# 03_SENSORS.net
KiCad netlist of a schematic drawn in Altium Designer
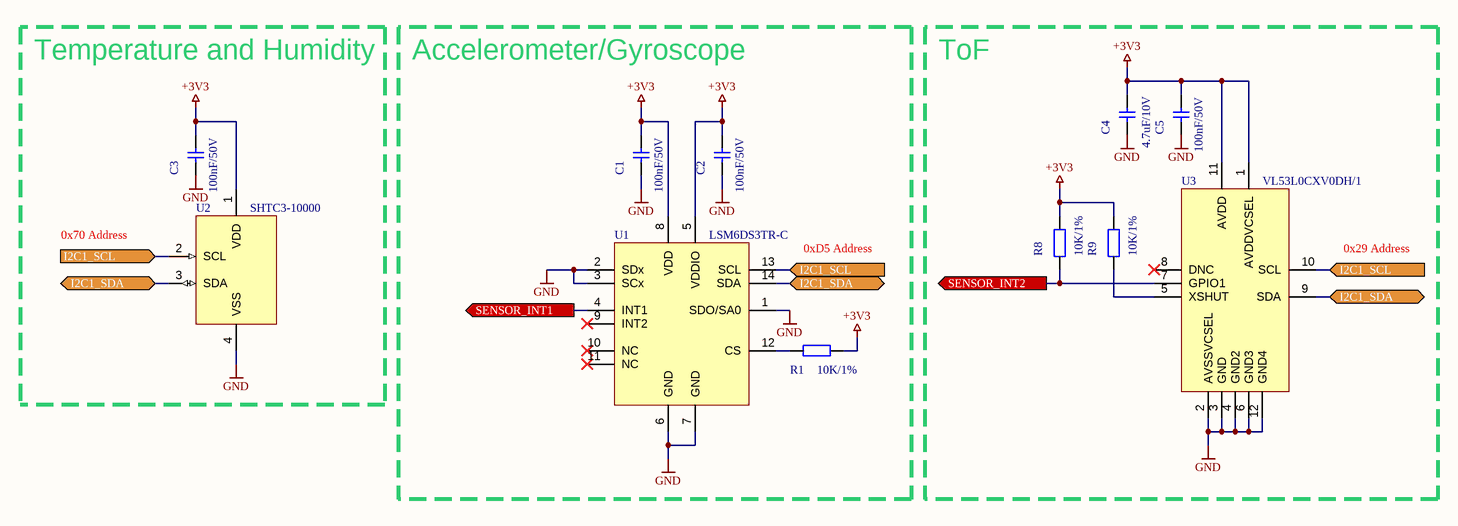
[diagram p0: 03 SENSORS.SchDoc]

(export (version "E")
  (design (tool "Eeschema 10.0.6"))
  (components
    (comp (ref "C1")
      (value "100nF/50V")
      (footprint "CAPC1005X06N")
      (description "16V 100nF X7R ±10% 0402  Multilayer Ceramic Capacitors MLCC - SMD/SMT ROHS")
      (fields
        (field (name "MANUFACTURER") "Samsung Electro-Mechanics")
        (field (name "MFR_PART_NUMBER") "CL05B104KO5NNNC")
      )
      (libsource (lib "altium_symbol") (part "CL05B104KO5NNNC"))
    )
    (comp (ref "C2")
      (value "100nF/50V")
      (footprint "CAPC1005X06N")
      (description "16V 100nF X7R ±10% 0402  Multilayer Ceramic Capacitors MLCC - SMD/SMT ROHS")
      (fields
        (field (name "MANUFACTURER") "Samsung Electro-Mechanics")
        (field (name "MFR_PART_NUMBER") "CL05B104KO5NNNC")
      )
      (libsource (lib "altium_symbol") (part "CL05B104KO5NNNC"))
    )
    (comp (ref "C3")
      (value "100nF/50V")
      (footprint "CAPC1005X06N")
      (description "16V 100nF X7R ±10% 0402  Multilayer Ceramic Capacitors MLCC - SMD/SMT ROHS")
      (fields
        (field (name "MANUFACTURER") "Samsung Electro-Mechanics")
        (field (name "MFR_PART_NUMBER") "CL05B104KO5NNNC")
      )
      (libsource (lib "altium_symbol") (part "CL05B104KO5NNNC"))
    )
    (comp (ref "C4")
      (value "4.7uF/10V")
      (footprint "CAPC1005X06N")
      (description "10V 4.7uF X5R ±20% 0402  Multilayer Ceramic Capacitors MLCC - SMD/SMT ROHS")
      (fields
        (field (name "MANUFACTURER") "Samsung Electro-Mechanics")
        (field (name "MFR_PART_NUMBER") "CL05A475MP5NRNC")
      )
      (libsource (lib "altium_symbol") (part "CL05A475MP5NRNC"))
    )
    (comp (ref "C5")
      (value "100nF/50V")
      (footprint "CAPC1005X06N")
      (description "16V 100nF X7R ±10% 0402  Multilayer Ceramic Capacitors MLCC - SMD/SMT ROHS")
      (fields
        (field (name "MANUFACTURER") "Samsung Electro-Mechanics")
        (field (name "MFR_PART_NUMBER") "CL05B104KO5NNNC")
      )
      (libsource (lib "altium_symbol") (part "CL05B104KO5NNNC"))
    )
    (comp (ref "R1")
      (value "10K/1%")
      (footprint "RESC1005X04N")
      (fields
        (field (name "MANUFACTURER") "UNI-ROYAL(Uniroyal Elec)")
        (field (name "MFR_PART_NUMBER") "0402WGF1002TCE")
      )
      (libsource (lib "altium_symbol") (part "0402WGF1002TCE"))
    )
    (comp (ref "R8")
      (value "10K/1%")
      (footprint "RESC1005X04N")
      (fields
        (field (name "MANUFACTURER") "UNI-ROYAL(Uniroyal Elec)")
        (field (name "MFR_PART_NUMBER") "0402WGF1002TCE")
      )
      (libsource (lib "altium_symbol") (part "0402WGF1002TCE"))
    )
    (comp (ref "R9")
      (value "10K/1%")
      (footprint "RESC1005X04N")
      (fields
        (field (name "MANUFACTURER") "UNI-ROYAL(Uniroyal Elec)")
        (field (name "MFR_PART_NUMBER") "0402WGF1002TCE")
      )
      (libsource (lib "altium_symbol") (part "0402WGF1002TCE"))
    )
    (comp (ref "U1")
      (value "LSM6DS3TR-C")
      (footprint "PQFN50P300X250X86-14N")
      (description "LGA-14L  Attitude Sensor/Gyroscope ROHS")
      (fields (field (name "MANUFACTURER") "STMicroelectronics"))
      (libsource (lib "altium_symbol") (part "LSM6DS3TR-C"))
    )
    (comp (ref "U2")
      (value "SHTC3-10000")
      (footprint "SON100P200X75_HS-5N")
      (description "DFN  Temperature and Humidity Sensor ROHS")
      (fields (field (name "MANUFACTURER") "Sensirion"))
      (libsource (lib "altium_symbol") (part "SHTC3-10000"))
    )
    (comp (ref "U3")
      (value "VL53L0CXV0DH/1")
      (footprint "VL53L0CXV0DH/1")
      (description "4.4*2.4*1.0mm  Position Sensor ROHS")
      (fields (field (name "MANUFACTURER") "STMicroelectronics"))
      (libsource (lib "altium_symbol") (part "VL53L0CXV0DH/1"))
    )
  )
  (nets
    (net (code "1") (name "+3V3") (class "Default")
      (node (ref "C1") (pin "2") (pinfunction "2_2") (pintype "passive"))
      (node (ref "C2") (pin "2") (pinfunction "2_2") (pintype "passive"))
      (node (ref "C3") (pin "2") (pinfunction "2_2") (pintype "passive"))
      (node (ref "C4") (pin "2") (pinfunction "2_2") (pintype "passive"))
      (node (ref "C5") (pin "2") (pinfunction "2_2") (pintype "passive"))
      (node (ref "R1") (pin "1") (pinfunction "1_1") (pintype "passive"))
      (node (ref "R8") (pin "1") (pinfunction "1_1") (pintype "passive"))
      (node (ref "R9") (pin "1") (pinfunction "1_1") (pintype "passive"))
      (node (ref "U1") (pin "5") (pinfunction "VDDIO_5") (pintype "passive"))
      (node (ref "U1") (pin "8") (pinfunction "VDD_8") (pintype "passive"))
      (node (ref "U2") (pin "1") (pinfunction "VDD_1") (pintype "passive"))
      (node (ref "U3") (pin "1") (pinfunction "AVDDVCSEL_1") (pintype "passive"))
      (node (ref "U3") (pin "11") (pinfunction "AVDD_11") (pintype "passive"))
    )
    (net (code "2") (name "/I2C1_SCL") (class "Default")
      (node (ref "U1") (pin "13") (pinfunction "SCL_13") (pintype "passive"))
      (node (ref "U2") (pin "2") (pinfunction "SCL_2") (pintype "input"))
      (node (ref "U3") (pin "10") (pinfunction "SCL_10") (pintype "passive"))
    )
    (net (code "3") (name "/I2C1_SDA") (class "Default")
      (node (ref "U1") (pin "14") (pinfunction "SDA_14") (pintype "passive"))
      (node (ref "U2") (pin "3") (pinfunction "SDA_3") (pintype "bidirectional"))
      (node (ref "U3") (pin "9") (pinfunction "SDA_9") (pintype "passive"))
    )
    (net (code "4") (name "/SENSOR_INT1") (class "Default")
      (node (ref "U1") (pin "4") (pinfunction "INT1_4") (pintype "passive"))
    )
    (net (code "5") (name "/SENSOR_INT2") (class "Default")
      (node (ref "R8") (pin "2") (pinfunction "2_2") (pintype "passive"))
      (node (ref "U3") (pin "7") (pinfunction "GPIO1_7") (pintype "passive"))
    )
    (net (code "6") (name "GND") (class "Default")
      (node (ref "C1") (pin "1") (pinfunction "1_1") (pintype "passive"))
      (node (ref "C2") (pin "1") (pinfunction "1_1") (pintype "passive"))
      (node (ref "C3") (pin "1") (pinfunction "1_1") (pintype "passive"))
      (node (ref "C4") (pin "1") (pinfunction "1_1") (pintype "passive"))
      (node (ref "C5") (pin "1") (pinfunction "1_1") (pintype "passive"))
      (node (ref "U1") (pin "1") (pinfunction "SDO/SA0_1") (pintype "passive"))
      (node (ref "U1") (pin "2") (pinfunction "SDx_2") (pintype "passive"))
      (node (ref "U1") (pin "3") (pinfunction "SCx_3") (pintype "passive"))
      (node (ref "U1") (pin "6") (pinfunction "GND_6") (pintype "passive"))
      (node (ref "U1") (pin "7") (pinfunction "GND_7") (pintype "passive"))
      (node (ref "U2") (pin "4") (pinfunction "VSS_4") (pintype "passive"))
      (node (ref "U3") (pin "12") (pinfunction "GND4_12") (pintype "passive"))
      (node (ref "U3") (pin "2") (pinfunction "AVSSVCSEL_2") (pintype "passive"))
      (node (ref "U3") (pin "3") (pinfunction "GND_3") (pintype "passive"))
      (node (ref "U3") (pin "4") (pinfunction "GND2_4") (pintype "passive"))
      (node (ref "U3") (pin "6") (pinfunction "GND3_6") (pintype "passive"))
    )
    (net (code "7") (name "Net-(U1-CS)") (class "Default")
      (node (ref "R1") (pin "2") (pinfunction "2_2") (pintype "passive"))
      (node (ref "U1") (pin "12") (pinfunction "CS_12") (pintype "passive"))
    )
    (net (code "8") (name "Net-(U3-XSHUT)") (class "Default")
      (node (ref "R9") (pin "2") (pinfunction "2_2") (pintype "passive"))
      (node (ref "U3") (pin "5") (pinfunction "XSHUT_5") (pintype "passive"))
    )
    (net (code "9") (name "unconnected-(U1-INT2-Pad9)") (class "Default")
      (node (ref "U1") (pin "9") (pinfunction "INT2_9") (pintype "passive+no_connect"))
    )
    (net (code "10") (name "unconnected-(U1-NC-Pad10)") (class "Default")
      (node (ref "U1") (pin "10") (pinfunction "NC_10") (pintype "passive+no_connect"))
    )
    (net (code "11") (name "unconnected-(U1-NC-Pad11)") (class "Default")
      (node (ref "U1") (pin "11") (pinfunction "NC_11") (pintype "passive+no_connect"))
    )
    (net (code "12") (name "unconnected-(U3-DNC-Pad8)") (class "Default")
      (node (ref "U3") (pin "8") (pinfunction "DNC_8") (pintype "passive+no_connect"))
    )
  )
)
